# FPGA_Config.net
KiCad netlist of a schematic drawn in Altium Designer
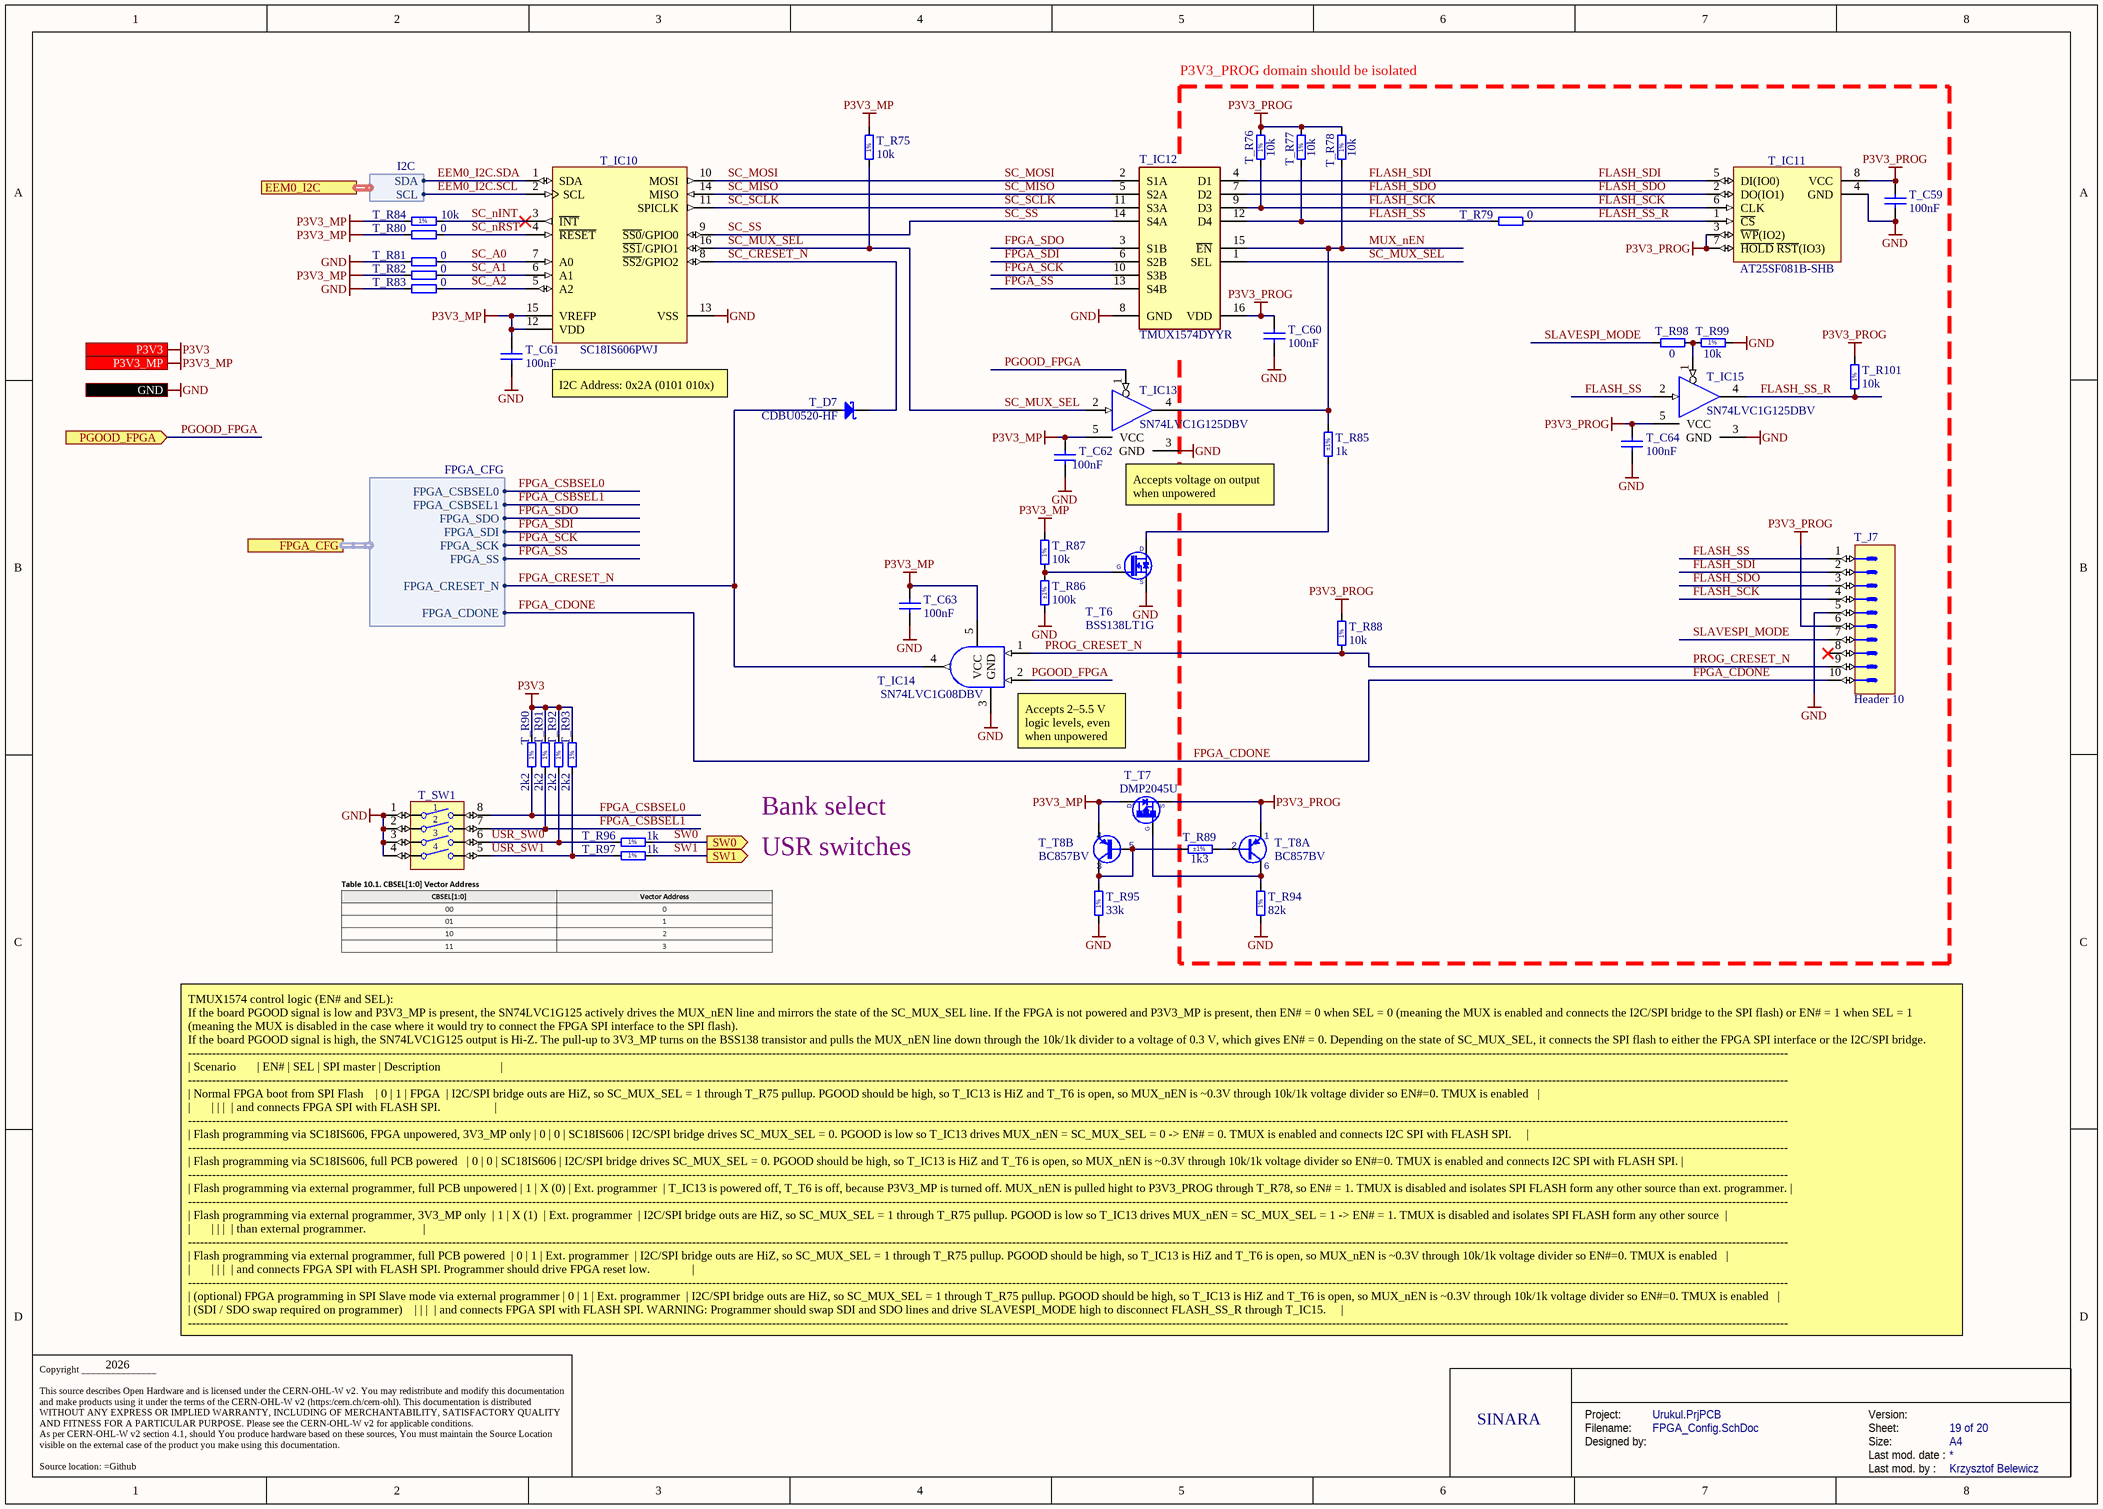
[diagram p0: FPGA_Config.SchDoc]

(export (version "E")
  (design (tool "Eeschema 10.0.6"))
  (components
    (comp (ref "T_C59")
      (value "100nF")
      (footprint "CAPC1005X55N")
      (description "Non-polarised capacitor")
      (fields
        (field (name "PART NUMBER") "CC0402_100NF_16V_10%_X5R")
        (field (name "VOLTAGE") "16V")
        (field (name "AUTHOR") "CERN DEM JLC")
      )
      (libsource (lib "Capacitors") (part "Capacitor - non polarized"))
    )
    (comp (ref "T_C60")
      (value "100nF")
      (footprint "CAPC1005X55N")
      (description "Non-polarised capacitor")
      (fields
        (field (name "PART NUMBER") "CC0402_100NF_16V_10%_X5R")
        (field (name "VOLTAGE") "16V")
        (field (name "AUTHOR") "CERN DEM JLC")
      )
      (libsource (lib "Capacitors") (part "Capacitor - non polarized"))
    )
    (comp (ref "T_C61")
      (value "100nF")
      (footprint "CAPC1005X55N")
      (description "Non-polarised capacitor")
      (fields
        (field (name "PART NUMBER") "CC0402_100NF_16V_10%_X5R")
        (field (name "VOLTAGE") "16V")
        (field (name "AUTHOR") "CERN DEM JLC")
      )
      (libsource (lib "Capacitors") (part "Capacitor - non polarized"))
    )
    (comp (ref "T_C62")
      (value "100nF")
      (footprint "CAPC1005X55N")
      (description "Non-polarised capacitor")
      (fields
        (field (name "PART NUMBER") "CC0402_100NF_16V_10%_X5R")
        (field (name "VOLTAGE") "16V")
        (field (name "AUTHOR") "CERN DEM JLC")
      )
      (libsource (lib "Capacitors") (part "Capacitor - non polarized"))
    )
    (comp (ref "T_C63")
      (value "100nF")
      (footprint "CAPC1005X55N")
      (description "Non-polarised capacitor")
      (fields
        (field (name "PART NUMBER") "CC0402_100NF_16V_10%_X5R")
        (field (name "VOLTAGE") "16V")
        (field (name "AUTHOR") "CERN DEM JLC")
      )
      (libsource (lib "Capacitors") (part "Capacitor - non polarized"))
    )
    (comp (ref "T_C64")
      (value "100nF")
      (footprint "CAPC1005X55N")
      (description "Non-polarised capacitor")
      (fields
        (field (name "PART NUMBER") "CC0402_100NF_16V_10%_X5R")
        (field (name "VOLTAGE") "16V")
        (field (name "AUTHOR") "CERN DEM JLC")
      )
      (libsource (lib "Capacitors") (part "Capacitor - non polarized"))
    )
    (comp (ref "T_D7")
      (value "CDBU0520-HF")
      (footprint "SOD-523F")
      (description "Schottky Diode")
      (fields
        (field (name "VOLTAGE") "20V")
        (field (name "POWER") "500mA")
        (field (name "AUTHOR") "CERN DEM HF")
      )
      (libsource (lib "ICs And Semiconductors") (part "Diode Schottky"))
    )
    (comp (ref "T_IC10")
      (value "SC18IS606PWJ")
      (footprint "SOP65P640X110-16N")
      (description "I2C-bus to SPI bridge")
      (fields (field (name "MANUFACTURER") "NXP SEMICONDUCTORS") (field (name "AUTHOR") "GK"))
      (libsource (lib "ICS-logic") (part "SC18IS606PWJ"))
    )
    (comp (ref "T_IC11")
      (value "AT25SF081B-SHB")
      (footprint "SOIC127P790X216-8N")
      (description "8M-bit Serial Flash Memory with uniform 4KB sectors and Dual/Quad SPI and QPI")
      (fields (field (name "MANUFACTURER") "Renesas") (field (name "AUTHOR") "GK"))
      (libsource (lib "ICS-logic") (part "MEM_AT25SF081B-SHB"))
    )
    (comp (ref "T_IC12")
      (value "TMUX1574DYYR")
      (footprint "SamacSys:SOP50P326X110-16N")
      (description "Integrated Circuit")
      (fields (field (name "MOUSER PART NUMBER") "595-TMUX1574DYYR"))
      (libsource (lib "SamacSys") (part "TMUX1574DYYR"))
    )
    (comp (ref "T_IC13")
      (value "SN74LVC1G125DBV")
      (footprint "SOT95P280X145-5N")
      (description "Single Bus Buffer Gate With 3-State Output")
      (fields (field (name "MANUFACTURER") "TEXAS INSTRUMENTS") (field (name "AUTHOR") "CERN DEM HF"))
      (libsource (lib "ICs And Semiconductors") (part "741G125"))
    )
    (comp (ref "T_IC14")
      (value "SN74LVC1G08DBV")
      (footprint "SOT95P280X145-5N")
      (description "Single 2-Input AND Gate")
      (fields (field (name "MANUFACTURER") "TEXAS INSTRUMENTS") (field (name "AUTHOR") "CERN DEM JLC"))
      (libsource (lib "ICs And Semiconductors") (part "741G08"))
    )
    (comp (ref "T_IC15")
      (value "SN74LVC1G125DBV")
      (footprint "SOT95P280X145-5N")
      (description "Single Bus Buffer Gate With 3-State Output")
      (fields (field (name "MANUFACTURER") "TEXAS INSTRUMENTS") (field (name "AUTHOR") "CERN DEM HF"))
      (libsource (lib "ICs And Semiconductors") (part "741G125"))
    )
    (comp (ref "T_J7")
      (value "Header 10")
      (footprint "HARWIN_M20-9980546")
      (description "Connector 10 Male")
      (fields
        (field (name "PART NUMBER") "HARWIN_M20-9980546")
        (field (name "MANUFACTURER") "HARWIN")
        (field (name "AUTHOR") "CERN DEM MR")
      )
      (libsource (lib "Connectors") (part "Connector 10 Male"))
    )
    (comp (ref "T_R75")
      (value "10k")
      (footprint "RESC1005X40N")
      (description "Resistor - 1%")
      (fields
        (field (name "PART NUMBER") "R0402_10K_1%_0.0625W_100PPM")
        (field (name "POWER") "0.0625W")
        (field (name "AUTHOR") "CERN DEM JLC")
      )
      (libsource (lib "Resistors") (part "Resistor - 1%"))
    )
    (comp (ref "T_R76")
      (value "10k")
      (footprint "RESC1005X40N")
      (description "Resistor - 1%")
      (fields
        (field (name "PART NUMBER") "R0402_10K_1%_0.0625W_100PPM")
        (field (name "POWER") "0.0625W")
        (field (name "AUTHOR") "CERN DEM JLC")
      )
      (libsource (lib "Resistors") (part "Resistor - 1%"))
    )
    (comp (ref "T_R77")
      (value "10k")
      (footprint "RESC1005X40N")
      (description "Resistor - 1%")
      (fields
        (field (name "PART NUMBER") "R0402_10K_1%_0.0625W_100PPM")
        (field (name "POWER") "0.0625W")
        (field (name "AUTHOR") "CERN DEM JLC")
      )
      (libsource (lib "Resistors") (part "Resistor - 1%"))
    )
    (comp (ref "T_R78")
      (value "10k")
      (footprint "RESC1005X40N")
      (description "Resistor - 1%")
      (fields
        (field (name "PART NUMBER") "R0402_10K_1%_0.0625W_100PPM")
        (field (name "POWER") "0.0625W")
        (field (name "AUTHOR") "CERN DEM JLC")
      )
      (libsource (lib "Resistors") (part "Resistor - 1%"))
    )
    (comp (ref "T_R79")
      (value "0")
      (footprint "RESC1005X40N")
      (description "Resistor")
      (fields
        (field (name "PART NUMBER") "R0402_0R_JUMPER")
        (field (name "MANUFACTURER") "GENERIC")
        (field (name "AUTHOR") "CERN DEM JLC")
      )
      (libsource (lib "Resistors") (part "Resistor"))
    )
    (comp (ref "T_R80")
      (value "0")
      (footprint "RESC1005X40N")
      (description "Resistor")
      (fields
        (field (name "PART NUMBER") "R0402_0R_JUMPER")
        (field (name "MANUFACTURER") "GENERIC")
        (field (name "AUTHOR") "CERN DEM JLC")
      )
      (libsource (lib "Resistors") (part "Resistor"))
    )
    (comp (ref "T_R81")
      (value "0")
      (footprint "RESC1005X40N")
      (description "Resistor")
      (fields
        (field (name "PART NUMBER") "R0402_0R_JUMPER")
        (field (name "MANUFACTURER") "GENERIC")
        (field (name "AUTHOR") "CERN DEM JLC")
      )
      (libsource (lib "Resistors") (part "Resistor"))
    )
    (comp (ref "T_R82")
      (value "0")
      (footprint "RESC1005X40N")
      (description "Resistor")
      (fields
        (field (name "PART NUMBER") "R0402_0R_JUMPER")
        (field (name "MANUFACTURER") "GENERIC")
        (field (name "AUTHOR") "CERN DEM JLC")
      )
      (libsource (lib "Resistors") (part "Resistor"))
    )
    (comp (ref "T_R83")
      (value "0")
      (footprint "RESC1005X40N")
      (description "Resistor")
      (fields
        (field (name "PART NUMBER") "R0402_0R_JUMPER")
        (field (name "MANUFACTURER") "GENERIC")
        (field (name "AUTHOR") "CERN DEM JLC")
      )
      (libsource (lib "Resistors") (part "Resistor"))
    )
    (comp (ref "T_R84")
      (value "10k")
      (footprint "RESC1005X40N")
      (description "Resistor - 1%")
      (fields
        (field (name "PART NUMBER") "R0402_10K_1%_0.0625W_100PPM")
        (field (name "POWER") "0.0625W")
        (field (name "AUTHOR") "CERN DEM JLC")
      )
      (libsource (lib "Resistors") (part "Resistor - 1%"))
    )
    (comp (ref "T_R85")
      (value "1k")
      (footprint "RESC1005X40N")
      (description "Resistor - 1%")
      (fields
        (field (name "TOLERANCE") "±1%")
        (field (name "PART NUMBER") "R0402_1K_1%_0.0625W_100PPM")
        (field (name "POWER") "0.0625W")
        (field (name "AUTHOR") "CERN DEM JLC")
      )
      (libsource (lib "Resistors") (part "Resistor - 1%"))
    )
    (comp (ref "T_R86")
      (value "100k")
      (footprint "RESC1005X40N")
      (description "Resistor - 1%")
      (fields
        (field (name "TOLERANCE") "±1%")
        (field (name "PART NUMBER") "R0402_100K_1%_0.0625W_100PPM")
        (field (name "POWER") "0.0625W")
        (field (name "AUTHOR") "CERN DEM JLC")
      )
      (libsource (lib "Resistors") (part "Resistor - 1%"))
    )
    (comp (ref "T_R87")
      (value "10k")
      (footprint "RESC1005X40N")
      (description "Resistor - 1%")
      (fields
        (field (name "PART NUMBER") "R0402_10K_1%_0.0625W_100PPM")
        (field (name "POWER") "0.0625W")
        (field (name "AUTHOR") "CERN DEM JLC")
      )
      (libsource (lib "Resistors") (part "Resistor - 1%"))
    )
    (comp (ref "T_R88")
      (value "10k")
      (footprint "RESC1005X40N")
      (description "Resistor - 1%")
      (fields
        (field (name "PART NUMBER") "R0402_10K_1%_0.0625W_100PPM")
        (field (name "POWER") "0.0625W")
        (field (name "AUTHOR") "CERN DEM JLC")
      )
      (libsource (lib "Resistors") (part "Resistor - 1%"))
    )
    (comp (ref "T_R89")
      (value "1k3")
      (footprint "RESC1005X40N")
      (description "Resistor - 1%")
      (fields
        (field (name "TOLERANCE") "±1%")
        (field (name "PART NUMBER") "R0402_1K3_1%_0.0625W_100PPM")
        (field (name "POWER") "0.0625W")
        (field (name "AUTHOR") "CERN DEM JLC")
      )
      (libsource (lib "Resistors") (part "Resistor - 1%"))
    )
    (comp (ref "T_R90")
      (value "2k2")
      (footprint "RESC1005X40N")
      (description "Resistor - 1%")
      (fields
        (field (name "PART NUMBER") "R0402_2K2_1%_0.0625W_100PPM")
        (field (name "POWER") "0.0625W")
        (field (name "AUTHOR") "CERN DEM JLC")
      )
      (libsource (lib "Resistors") (part "Resistor - 1%"))
    )
    (comp (ref "T_R91")
      (value "2k2")
      (footprint "RESC1005X40N")
      (description "Resistor - 1%")
      (fields
        (field (name "PART NUMBER") "R0402_2K2_1%_0.0625W_100PPM")
        (field (name "POWER") "0.0625W")
        (field (name "AUTHOR") "CERN DEM JLC")
      )
      (libsource (lib "Resistors") (part "Resistor - 1%"))
    )
    (comp (ref "T_R92")
      (value "2k2")
      (footprint "RESC1005X40N")
      (description "Resistor - 1%")
      (fields
        (field (name "PART NUMBER") "R0402_2K2_1%_0.0625W_100PPM")
        (field (name "POWER") "0.0625W")
        (field (name "AUTHOR") "CERN DEM JLC")
      )
      (libsource (lib "Resistors") (part "Resistor - 1%"))
    )
    (comp (ref "T_R93")
      (value "2k2")
      (footprint "RESC1005X40N")
      (description "Resistor - 1%")
      (fields
        (field (name "PART NUMBER") "R0402_2K2_1%_0.0625W_100PPM")
        (field (name "POWER") "0.0625W")
        (field (name "AUTHOR") "CERN DEM JLC")
      )
      (libsource (lib "Resistors") (part "Resistor - 1%"))
    )
    (comp (ref "T_R94")
      (value "82k")
      (footprint "RESC1608X55N")
      (description "Resistor - 1%")
      (fields
        (field (name "PART NUMBER") "R0603_82K_1%_0.1W_100PPM")
        (field (name "POWER") "0.1W")
        (field (name "AUTHOR") "CERN DEM JLC")
      )
      (libsource (lib "Resistors") (part "Resistor - 1%"))
    )
    (comp (ref "T_R95")
      (value "33k")
      (footprint "RESC1005X40N")
      (description "Resistor - 1%")
      (fields
        (field (name "PART NUMBER") "R0402_33K_1%_0.0625W_100PPM")
        (field (name "POWER") "0.0625W")
        (field (name "AUTHOR") "CERN DEM JLC")
      )
      (libsource (lib "Resistors") (part "Resistor - 1%"))
    )
    (comp (ref "T_R96")
      (value "1k")
      (footprint "RESC1005X40N")
      (description "Resistor - 1%")
      (fields
        (field (name "PART NUMBER") "R0402_1K_1%_0.0625W_100PPM")
        (field (name "POWER") "0.0625W")
        (field (name "AUTHOR") "CERN DEM JLC")
      )
      (libsource (lib "Resistors") (part "Resistor - 1%"))
    )
    (comp (ref "T_R97")
      (value "1k")
      (footprint "RESC1005X40N")
      (description "Resistor - 1%")
      (fields
        (field (name "PART NUMBER") "R0402_1K_1%_0.0625W_100PPM")
        (field (name "POWER") "0.0625W")
        (field (name "AUTHOR") "CERN DEM JLC")
      )
      (libsource (lib "Resistors") (part "Resistor - 1%"))
    )
    (comp (ref "T_R98")
      (value "0")
      (footprint "RESC1005X40N")
      (description "Resistor")
      (fields
        (field (name "PART NUMBER") "R0402_0R_JUMPER")
        (field (name "MANUFACTURER") "GENERIC")
        (field (name "AUTHOR") "CERN DEM JLC")
      )
      (libsource (lib "Resistors") (part "Resistor"))
    )
    (comp (ref "T_R99")
      (value "10k")
      (footprint "RESC1005X40N")
      (description "Resistor - 1%")
      (fields
        (field (name "PART NUMBER") "R0402_10K_1%_0.0625W_100PPM")
        (field (name "POWER") "0.0625W")
        (field (name "AUTHOR") "CERN DEM JLC")
      )
      (libsource (lib "Resistors") (part "Resistor - 1%"))
    )
    (comp (ref "T_R101")
      (value "10k")
      (footprint "RESC1005X40N")
      (description "Resistor - 1%")
      (fields
        (field (name "PART NUMBER") "R0402_10K_1%_0.0625W_100PPM")
        (field (name "POWER") "0.0625W")
        (field (name "AUTHOR") "CERN DEM JLC")
      )
      (libsource (lib "Resistors") (part "Resistor - 1%"))
    )
    (comp (ref "T_SW1")
      (value "Switch")
      (footprint "SW_TYCO_1571983-4")
      (description "4 Ways SPST DIP Switch")
      (fields
        (field (name "PART NUMBER") "SW_TYCO_1571983-4")
        (field (name "MANUFACTURER") "TYCO")
        (field (name "AUTHOR") "CERN DEM JLC")
      )
      (libsource (lib "Eletro-mechanical") (part "SW 4x SPST DIP Switch"))
    )
    (comp (ref "T_T6")
      (value "BSS138LT1G")
      (footprint "SOT95P240X110-3N")
      (description "N-CHANNEL MOSFET WITH DIODE")
      (fields
        (field (name "MANUFACTURER") "ON SEMICONDUCTOR")
        (field (name "MANUFACTURER PART NUMBER") "BSS138L")
        (field (name "AUTHOR") "CERN DEM JLC")
      )
      (libsource (lib "ICs And Semiconductors") (part "N-MOSFET-D 1G 2S 3D"))
    )
    (comp (ref "T_T7")
      (value "DMP2045U")
      (footprint "SOT95P240X110-3N")
      (description "P-CHANNEL MOSFET WITH DIODE")
      (fields (field (name "MANUFACTURER") "DIODES INCORPORATED") (field (name "AUTHOR") "CERN DEM HF"))
      (libsource (lib "ICs And Semiconductors") (part "P-MOSFET-D 1G 2S 3D"))
    )
    (comp (ref "T_T8")
      (value "BC857BV")
      (footprint "SOTFL50P160X60-6N")
      (description "45V, 100mA PNP General Purpose Double Transistor")
      (fields (field (name "MANUFACTURER") "NXP SEMICONDUCTORS") (field (name "AUTHOR") "CERN DEM JLC"))
      (libsource (lib "ICs And Semiconductors") (part "BC857BV"))
    )
  )
  (nets
    (net (code "3") (name "/EEM0_I2C.SCL") (class "Default")
      (node (ref "T_IC10") (pin "2") (pinfunction "SCL_2") (pintype "input"))
    )
    (net (code "4") (name "/EEM0_I2C.SDA") (class "Default")
      (node (ref "T_IC10") (pin "1") (pinfunction "SDA_1") (pintype "bidirectional"))
    )
    (net (code "5") (name "/FLASH_SCK") (class "Default")
      (node (ref "T_IC11") (pin "6") (pinfunction "CLK_6") (pintype "input"))
      (node (ref "T_IC12") (pin "9") (pinfunction "D3_9") (pintype "passive"))
      (node (ref "T_J7") (pin "4") (pinfunction "4_4") (pintype "bidirectional"))
      (node (ref "T_R76") (pin "1") (pinfunction "1_1") (pintype "passive"))
    )
    (net (code "6") (name "/FLASH_SDI") (class "Default")
      (node (ref "T_IC11") (pin "5") (pinfunction "DI(IO0)_5") (pintype "bidirectional"))
      (node (ref "T_IC12") (pin "4") (pinfunction "D1_4") (pintype "passive"))
      (node (ref "T_J7") (pin "2") (pinfunction "2_2") (pintype "bidirectional"))
    )
    (net (code "7") (name "/FLASH_SDO") (class "Default")
      (node (ref "T_IC11") (pin "2") (pinfunction "DO(IO1)_2") (pintype "bidirectional"))
      (node (ref "T_IC12") (pin "7") (pinfunction "D2_7") (pintype "passive"))
      (node (ref "T_J7") (pin "3") (pinfunction "3_3") (pintype "bidirectional"))
    )
    (net (code "8") (name "/FLASH_SS") (class "Default")
      (node (ref "T_IC12") (pin "12") (pinfunction "D4_12") (pintype "passive"))
      (node (ref "T_IC15") (pin "2") (pinfunction "IN_2") (pintype "input"))
      (node (ref "T_J7") (pin "1") (pinfunction "1_1") (pintype "bidirectional"))
      (node (ref "T_R77") (pin "1") (pinfunction "1_1") (pintype "passive"))
      (node (ref "T_R79") (pin "1") (pinfunction "1_1") (pintype "passive"))
    )
    (net (code "9") (name "/FLASH_SS_R") (class "Default")
      (node (ref "T_IC11") (pin "1") (pinfunction "~{CS}_1") (pintype "input"))
      (node (ref "T_IC15") (pin "4") (pinfunction "OUT_4") (pintype "tri_state"))
      (node (ref "T_R101") (pin "1") (pinfunction "1_1") (pintype "passive"))
      (node (ref "T_R79") (pin "2") (pinfunction "2_2") (pintype "passive"))
    )
    (net (code "10") (name "/FPGA_CDONE") (class "Default")
      (node (ref "T_J7") (pin "10") (pinfunction "10_10") (pintype "bidirectional"))
    )
    (net (code "11") (name "/FPGA_CRESET_N") (class "Default")
      (node (ref "T_D7") (pin "2") (pinfunction "A_2") (pintype "passive"))
      (node (ref "T_IC14") (pin "4") (pinfunction "Y_4") (pintype "output"))
    )
    (net (code "12") (name "/FPGA_CSBSEL0") (class "Default")
      (node (ref "T_R90") (pin "1") (pinfunction "1_1") (pintype "passive"))
      (node (ref "T_SW1") (pin "8") (pinfunction "8_8") (pintype "bidirectional"))
    )
    (net (code "13") (name "/FPGA_CSBSEL1") (class "Default")
      (node (ref "T_R91") (pin "1") (pinfunction "1_1") (pintype "passive"))
      (node (ref "T_SW1") (pin "7") (pinfunction "7_7") (pintype "bidirectional"))
    )
    (net (code "14") (name "/FPGA_SCK") (class "Default")
      (node (ref "T_IC12") (pin "10") (pinfunction "S3B_10") (pintype "passive"))
    )
    (net (code "15") (name "/FPGA_SDI") (class "Default")
      (node (ref "T_IC12") (pin "6") (pinfunction "S2B_6") (pintype "passive"))
    )
    (net (code "16") (name "/FPGA_SDO") (class "Default")
      (node (ref "T_IC12") (pin "3") (pinfunction "S1B_3") (pintype "passive"))
    )
    (net (code "17") (name "/FPGA_SS") (class "Default")
      (node (ref "T_IC12") (pin "13") (pinfunction "S4B_13") (pintype "passive"))
    )
    (net (code "18") (name "/MUX_nEN") (class "Default")
      (node (ref "T_IC12") (pin "15") (pinfunction "~{EN}_15") (pintype "passive"))
      (node (ref "T_IC13") (pin "4") (pinfunction "OUT_4") (pintype "tri_state"))
      (node (ref "T_R78") (pin "1") (pinfunction "1_1") (pintype "passive"))
      (node (ref "T_R85") (pin "2") (pinfunction "2_2") (pintype "passive"))
    )
    (net (code "19") (name "/PGOOD_FPGA") (class "Default")
      (node (ref "T_IC13") (pin "1") (pinfunction "~{G}_1") (pintype "input"))
      (node (ref "T_IC14") (pin "2") (pinfunction "B_2") (pintype "input"))
    )
    (net (code "20") (name "/PROG_CRESET_N") (class "Default")
      (node (ref "T_IC14") (pin "1") (pinfunction "A_1") (pintype "input"))
      (node (ref "T_J7") (pin "9") (pinfunction "9_9") (pintype "bidirectional"))
      (node (ref "T_R88") (pin "1") (pinfunction "1_1") (pintype "passive"))
    )
    (net (code "21") (name "/SC_A0") (class "Default")
      (node (ref "T_IC10") (pin "7") (pinfunction "A0_7") (pintype "input"))
      (node (ref "T_R81") (pin "1") (pinfunction "1_1") (pintype "passive"))
    )
    (net (code "22") (name "/SC_A1") (class "Default")
      (node (ref "T_IC10") (pin "6") (pinfunction "A1_6") (pintype "input"))
      (node (ref "T_R82") (pin "1") (pinfunction "1_1") (pintype "passive"))
    )
    (net (code "23") (name "/SC_A2") (class "Default")
      (node (ref "T_IC10") (pin "5") (pinfunction "A2_5") (pintype "bidirectional"))
      (node (ref "T_R83") (pin "1") (pinfunction "1_1") (pintype "passive"))
    )
    (net (code "24") (name "/SC_CRESET_N") (class "Default")
      (node (ref "T_D7") (pin "1") (pinfunction "C_1") (pintype "passive"))
      (node (ref "T_IC10") (pin "8") (pinfunction "~{SS2}/GPIO2_8") (pintype "bidirectional"))
    )
    (net (code "25") (name "/SC_MISO") (class "Default")
      (node (ref "T_IC10") (pin "14") (pinfunction "MISO_14") (pintype "input"))
      (node (ref "T_IC12") (pin "5") (pinfunction "S2A_5") (pintype "passive"))
    )
    (net (code "26") (name "/SC_MOSI") (class "Default")
      (node (ref "T_IC10") (pin "10") (pinfunction "MOSI_10") (pintype "output"))
      (node (ref "T_IC12") (pin "2") (pinfunction "S1A_2") (pintype "passive"))
    )
    (net (code "27") (name "/SC_MUX_SEL") (class "Default")
      (node (ref "T_IC10") (pin "16") (pinfunction "~{SS1}/GPIO1_16") (pintype "bidirectional"))
      (node (ref "T_IC12") (pin "1") (pinfunction "SEL_1") (pintype "passive"))
      (node (ref "T_IC13") (pin "2") (pinfunction "IN_2") (pintype "input"))
      (node (ref "T_R75") (pin "1") (pinfunction "1_1") (pintype "passive"))
    )
    (net (code "28") (name "/SC_SCLK") (class "Default")
      (node (ref "T_IC10") (pin "11") (pinfunction "SPICLK_11") (pintype "output"))
      (node (ref "T_IC12") (pin "11") (pinfunction "S3A_11") (pintype "passive"))
    )
    (net (code "29") (name "/SC_SS") (class "Default")
      (node (ref "T_IC10") (pin "9") (pinfunction "~{SS0}/GPIO0_9") (pintype "bidirectional"))
      (node (ref "T_IC12") (pin "14") (pinfunction "S4A_14") (pintype "passive"))
    )
    (net (code "30") (name "/SC_nINT") (class "Default")
      (node (ref "T_IC10") (pin "3") (pinfunction "~{INT}_3") (pintype "output"))
      (node (ref "T_R84") (pin "2") (pinfunction "2_2") (pintype "passive"))
    )
    (net (code "31") (name "/SC_nRST") (class "Default")
      (node (ref "T_IC10") (pin "4") (pinfunction "~{RESET}_4") (pintype "input"))
      (node (ref "T_R80") (pin "1") (pinfunction "1_1") (pintype "passive"))
    )
    (net (code "32") (name "/SLAVESPI_MODE") (class "Default")
      (node (ref "T_J7") (pin "7") (pinfunction "7_7") (pintype "bidirectional"))
      (node (ref "T_R98") (pin "1") (pinfunction "1_1") (pintype "passive"))
    )
    (net (code "33") (name "/SW0") (class "Default")
      (node (ref "T_R96") (pin "1") (pinfunction "1_1") (pintype "passive"))
    )
    (net (code "34") (name "/SW1") (class "Default")
      (node (ref "T_R97") (pin "1") (pinfunction "1_1") (pintype "passive"))
    )
    (net (code "35") (name "/USR_SW0") (class "Default")
      (node (ref "T_R92") (pin "1") (pinfunction "1_1") (pintype "passive"))
      (node (ref "T_R96") (pin "2") (pinfunction "2_2") (pintype "passive"))
      (node (ref "T_SW1") (pin "6") (pinfunction "6_6") (pintype "bidirectional"))
    )
    (net (code "36") (name "/USR_SW1") (class "Default")
      (node (ref "T_R93") (pin "1") (pinfunction "1_1") (pintype "passive"))
      (node (ref "T_R97") (pin "2") (pinfunction "2_2") (pintype "passive"))
      (node (ref "T_SW1") (pin "5") (pinfunction "5_5") (pintype "bidirectional"))
    )
    (net (code "39") (name "GND") (class "Default")
      (node (ref "T_C59") (pin "1") (pinfunction "1_1") (pintype "passive"))
      (node (ref "T_C60") (pin "1") (pinfunction "1_1") (pintype "passive"))
      (node (ref "T_C61") (pin "1") (pinfunction "1_1") (pintype "passive"))
      (node (ref "T_C62") (pin "1") (pinfunction "1_1") (pintype "passive"))
      (node (ref "T_C63") (pin "1") (pinfunction "1_1") (pintype "passive"))
      (node (ref "T_C64") (pin "1") (pinfunction "1_1") (pintype "passive"))
      (node (ref "T_IC10") (pin "13") (pinfunction "VSS_13") (pintype "power_in"))
      (node (ref "T_IC11") (pin "4") (pinfunction "GND_4") (pintype "power_in"))
      (node (ref "T_IC12") (pin "8") (pinfunction "GND_8") (pintype "passive"))
      (node (ref "T_IC13") (pin "3") (pinfunction "GND_3") (pintype "power_in"))
      (node (ref "T_IC14") (pin "3") (pinfunction "GND_3") (pintype "power_in"))
      (node (ref "T_IC15") (pin "3") (pinfunction "GND_3") (pintype "power_in"))
      (node (ref "T_J7") (pin "5") (pinfunction "5_5") (pintype "bidirectional"))
      (node (ref "T_R81") (pin "2") (pinfunction "2_2") (pintype "passive"))
      (node (ref "T_R83") (pin "2") (pinfunction "2_2") (pintype "passive"))
      (node (ref "T_R86") (pin "2") (pinfunction "2_2") (pintype "passive"))
      (node (ref "T_R94") (pin "1") (pinfunction "1_1") (pintype "passive"))
      (node (ref "T_R95") (pin "1") (pinfunction "1_1") (pintype "passive"))
      (node (ref "T_R99") (pin "2") (pinfunction "2_2") (pintype "passive"))
      (node (ref "T_SW1") (pin "1") (pinfunction "1_1") (pintype "bidirectional"))
      (node (ref "T_SW1") (pin "2") (pinfunction "2_2") (pintype "bidirectional"))
      (node (ref "T_SW1") (pin "3") (pinfunction "3_3") (pintype "bidirectional"))
      (node (ref "T_SW1") (pin "4") (pinfunction "4_4") (pintype "bidirectional"))
      (node (ref "T_T6") (pin "2") (pinfunction "S_2") (pintype "passive"))
    )
    (net (code "40") (name "Net-(T_IC15-~{G})") (class "Default")
      (node (ref "T_IC15") (pin "1") (pinfunction "~{G}_1") (pintype "input"))
      (node (ref "T_R98") (pin "2") (pinfunction "2_2") (pintype "passive"))
      (node (ref "T_R99") (pin "1") (pinfunction "1_1") (pintype "passive"))
    )
    (net (code "41") (name "Net-(T_T6-D)") (class "Default")
      (node (ref "T_R85") (pin "1") (pinfunction "1_1") (pintype "passive"))
      (node (ref "T_T6") (pin "3") (pinfunction "D_3") (pintype "passive"))
    )
    (net (code "42") (name "Net-(T_T6-G)") (class "Default")
      (node (ref "T_R86") (pin "1") (pinfunction "1_1") (pintype "passive"))
      (node (ref "T_R87") (pin "1") (pinfunction "1_1") (pintype "passive"))
      (node (ref "T_T6") (pin "1") (pinfunction "G_1") (pintype "passive"))
    )
    (net (code "43") (name "Net-(T_T7-G)") (class "Default")
      (node (ref "T_R94") (pin "2") (pinfunction "2_2") (pintype "passive"))
      (node (ref "T_T7") (pin "1") (pinfunction "G_1") (pintype "passive"))
      (node (ref "T_T8") (pin "6") (pinfunction "C_6") (pintype "passive"))
    )
    (net (code "44") (name "Net-(T_T8A-B)") (class "Default")
      (node (ref "T_R89") (pin "1") (pinfunction "1_1") (pintype "passive"))
      (node (ref "T_T8") (pin "2") (pinfunction "B_2") (pintype "passive"))
    )
    (net (code "45") (name "Net-(T_T8B-B)") (class "Default")
      (node (ref "T_R89") (pin "2") (pinfunction "2_2") (pintype "passive"))
      (node (ref "T_R95") (pin "2") (pinfunction "2_2") (pintype "passive"))
      (node (ref "T_T8") (pin "3") (pinfunction "C_3") (pintype "passive"))
      (node (ref "T_T8") (pin "5") (pinfunction "B_5") (pintype "passive"))
    )
    (net (code "46") (name "P3V3") (class "Default")
      (node (ref "T_R90") (pin "2") (pinfunction "2_2") (pintype "passive"))
      (node (ref "T_R91") (pin "2") (pinfunction "2_2") (pintype "passive"))
      (node (ref "T_R92") (pin "2") (pinfunction "2_2") (pintype "passive"))
      (node (ref "T_R93") (pin "2") (pinfunction "2_2") (pintype "passive"))
    )
    (net (code "47") (name "P3V3_MP") (class "Default")
      (node (ref "T_C61") (pin "2") (pinfunction "2_2") (pintype "passive"))
      (node (ref "T_C62") (pin "2") (pinfunction "2_2") (pintype "passive"))
      (node (ref "T_C63") (pin "2") (pinfunction "2_2") (pintype "passive"))
      (node (ref "T_IC10") (pin "12") (pinfunction "VDD_12") (pintype "power_in"))
      (node (ref "T_IC10") (pin "15") (pinfunction "VREFP_15") (pintype "power_in"))
      (node (ref "T_IC13") (pin "5") (pinfunction "VCC_5") (pintype "power_in"))
      (node (ref "T_IC14") (pin "5") (pinfunction "VCC_5") (pintype "power_in"))
      (node (ref "T_R75") (pin "2") (pinfunction "2_2") (pintype "passive"))
      (node (ref "T_R80") (pin "2") (pinfunction "2_2") (pintype "passive"))
      (node (ref "T_R82") (pin "2") (pinfunction "2_2") (pintype "passive"))
      (node (ref "T_R84") (pin "1") (pinfunction "1_1") (pintype "passive"))
      (node (ref "T_R87") (pin "2") (pinfunction "2_2") (pintype "passive"))
      (node (ref "T_T7") (pin "3") (pinfunction "D_3") (pintype "passive"))
      (node (ref "T_T8") (pin "4") (pinfunction "E_4") (pintype "passive"))
    )
    (net (code "48") (name "P3V3_PROG") (class "Default")
      (node (ref "T_C59") (pin "2") (pinfunction "2_2") (pintype "passive"))
      (node (ref "T_C60") (pin "2") (pinfunction "2_2") (pintype "passive"))
      (node (ref "T_C64") (pin "2") (pinfunction "2_2") (pintype "passive"))
      (node (ref "T_IC11") (pin "3") (pinfunction "~{WP}(IO2)_3") (pintype "bidirectional"))
      (node (ref "T_IC11") (pin "7") (pinfunction "~{HOLD}_~{RST}(IO3)_7") (pintype "bidirectional"))
      (node (ref "T_IC11") (pin "8") (pinfunction "VCC_8") (pintype "power_in"))
      (node (ref "T_IC12") (pin "16") (pinfunction "VDD_16") (pintype "passive"))
      (node (ref "T_IC15") (pin "5") (pinfunction "VCC_5") (pintype "power_in"))
      (node (ref "T_J7") (pin "6") (pinfunction "6_6") (pintype "bidirectional"))
      (node (ref "T_R101") (pin "2") (pinfunction "2_2") (pintype "passive"))
      (node (ref "T_R76") (pin "2") (pinfunction "2_2") (pintype "passive"))
      (node (ref "T_R77") (pin "2") (pinfunction "2_2") (pintype "passive"))
      (node (ref "T_R78") (pin "2") (pinfunction "2_2") (pintype "passive"))
      (node (ref "T_R88") (pin "2") (pinfunction "2_2") (pintype "passive"))
      (node (ref "T_T7") (pin "2") (pinfunction "S_2") (pintype "passive"))
      (node (ref "T_T8") (pin "1") (pinfunction "E_1") (pintype "passive"))
    )
    (net (code "49") (name "unconnected-(T_J7-Pad8)") (class "Default")
      (node (ref "T_J7") (pin "8") (pinfunction "8_8") (pintype "bidirectional+no_connect"))
    )
  )
)
